# Test01.net
KiCad netlist of a schematic drawn in EasyEDA
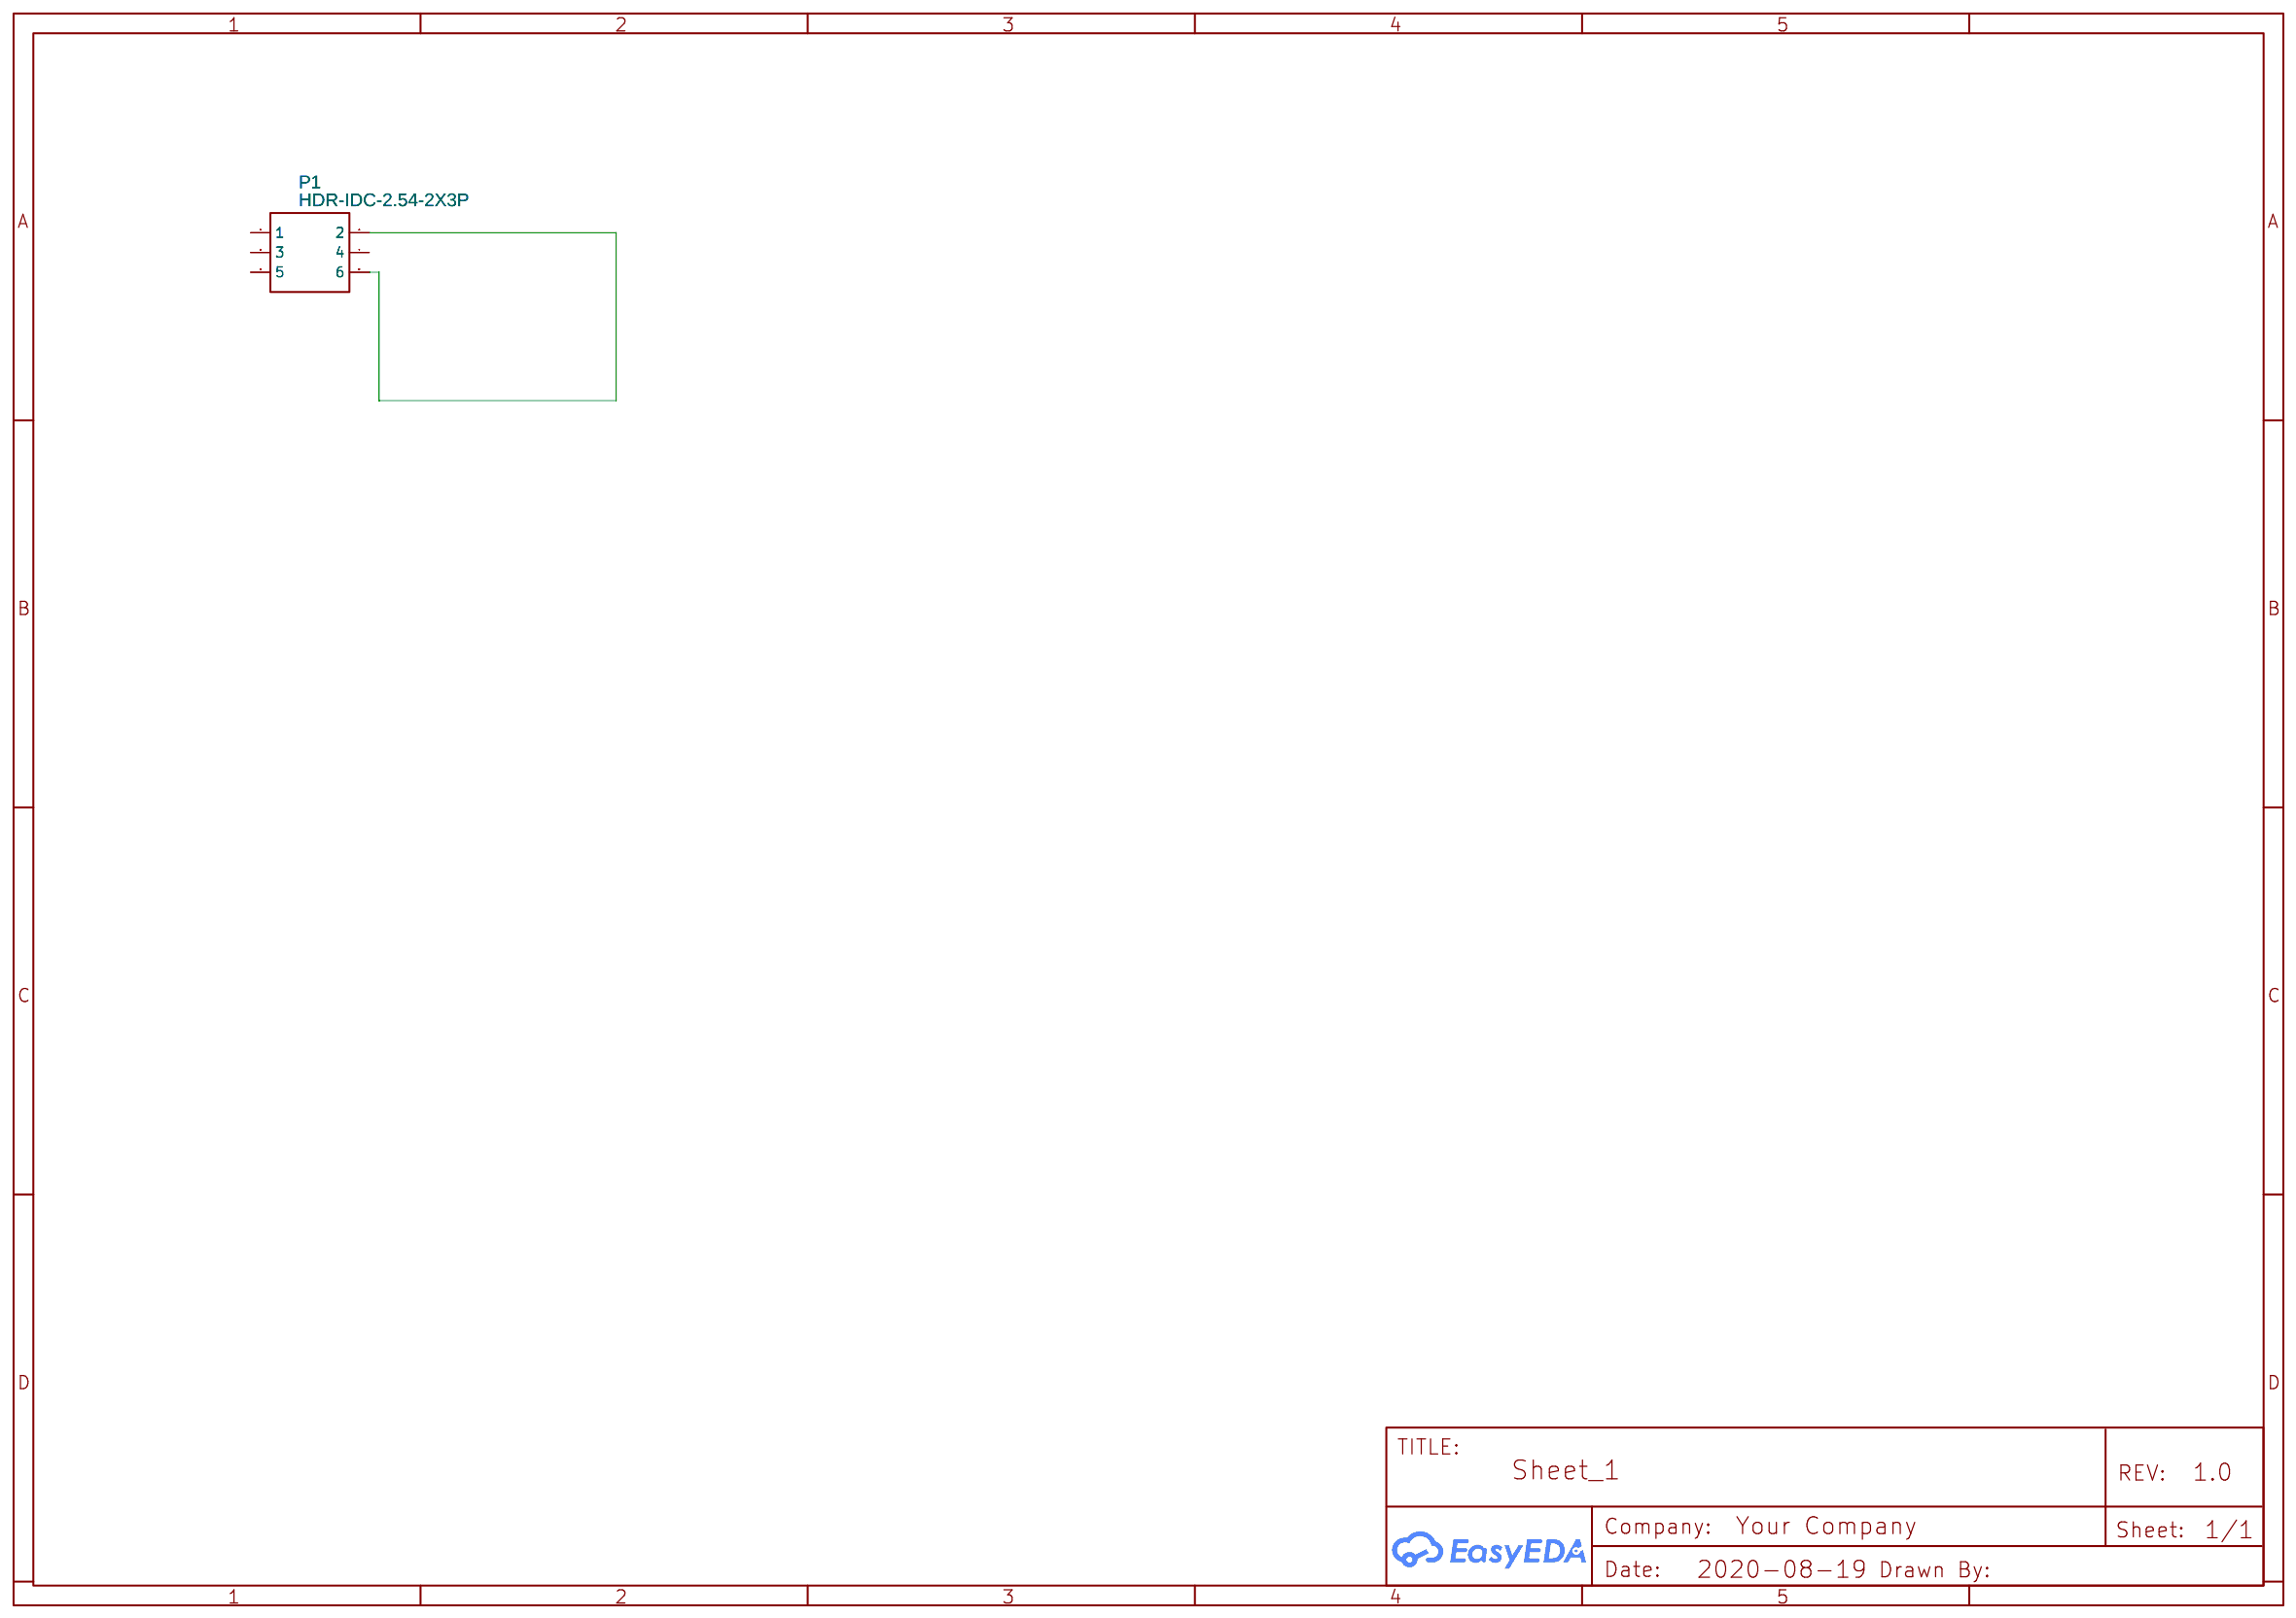
[diagram p0: schematic sheet]

(export (version "E")
  (design (tool "Eeschema 10.0.6"))
  (components
    (comp (ref "P1")
      (value "HDR-IDC-2.54-2X3P")
      (fields
        (field (name "BOM_Manufacturer Part") "2X3 2.54mm IDC Box")
        (field (name "BOM_Supplier Part") "C11214")
      )
      (libsource (lib "") (part "HDR-IDC-2.54-2X3P"))
    )
  )
  (nets
    (net (code "1") (name "Net-(P1-Pad2)") (class "Default")
      (node (ref "P1") (pin "2") (pinfunction "2_2") (pintype "unspecified"))
      (node (ref "P1") (pin "6") (pinfunction "6_6") (pintype "unspecified"))
    )
    (net (code "2") (name "unconnected-(P1-Pad1)") (class "Default")
      (node (ref "P1") (pin "1") (pinfunction "1_1") (pintype "unspecified"))
    )
    (net (code "3") (name "unconnected-(P1-Pad3)") (class "Default")
      (node (ref "P1") (pin "3") (pinfunction "3_3") (pintype "unspecified"))
    )
    (net (code "4") (name "unconnected-(P1-Pad4)") (class "Default")
      (node (ref "P1") (pin "4") (pinfunction "4_4") (pintype "unspecified"))
    )
    (net (code "5") (name "unconnected-(P1-Pad5)") (class "Default")
      (node (ref "P1") (pin "5") (pinfunction "5_5") (pintype "unspecified"))
    )
  )
)
